# 1-Schematic_final_7_3d.net
KiCad netlist of a schematic drawn in EasyEDA
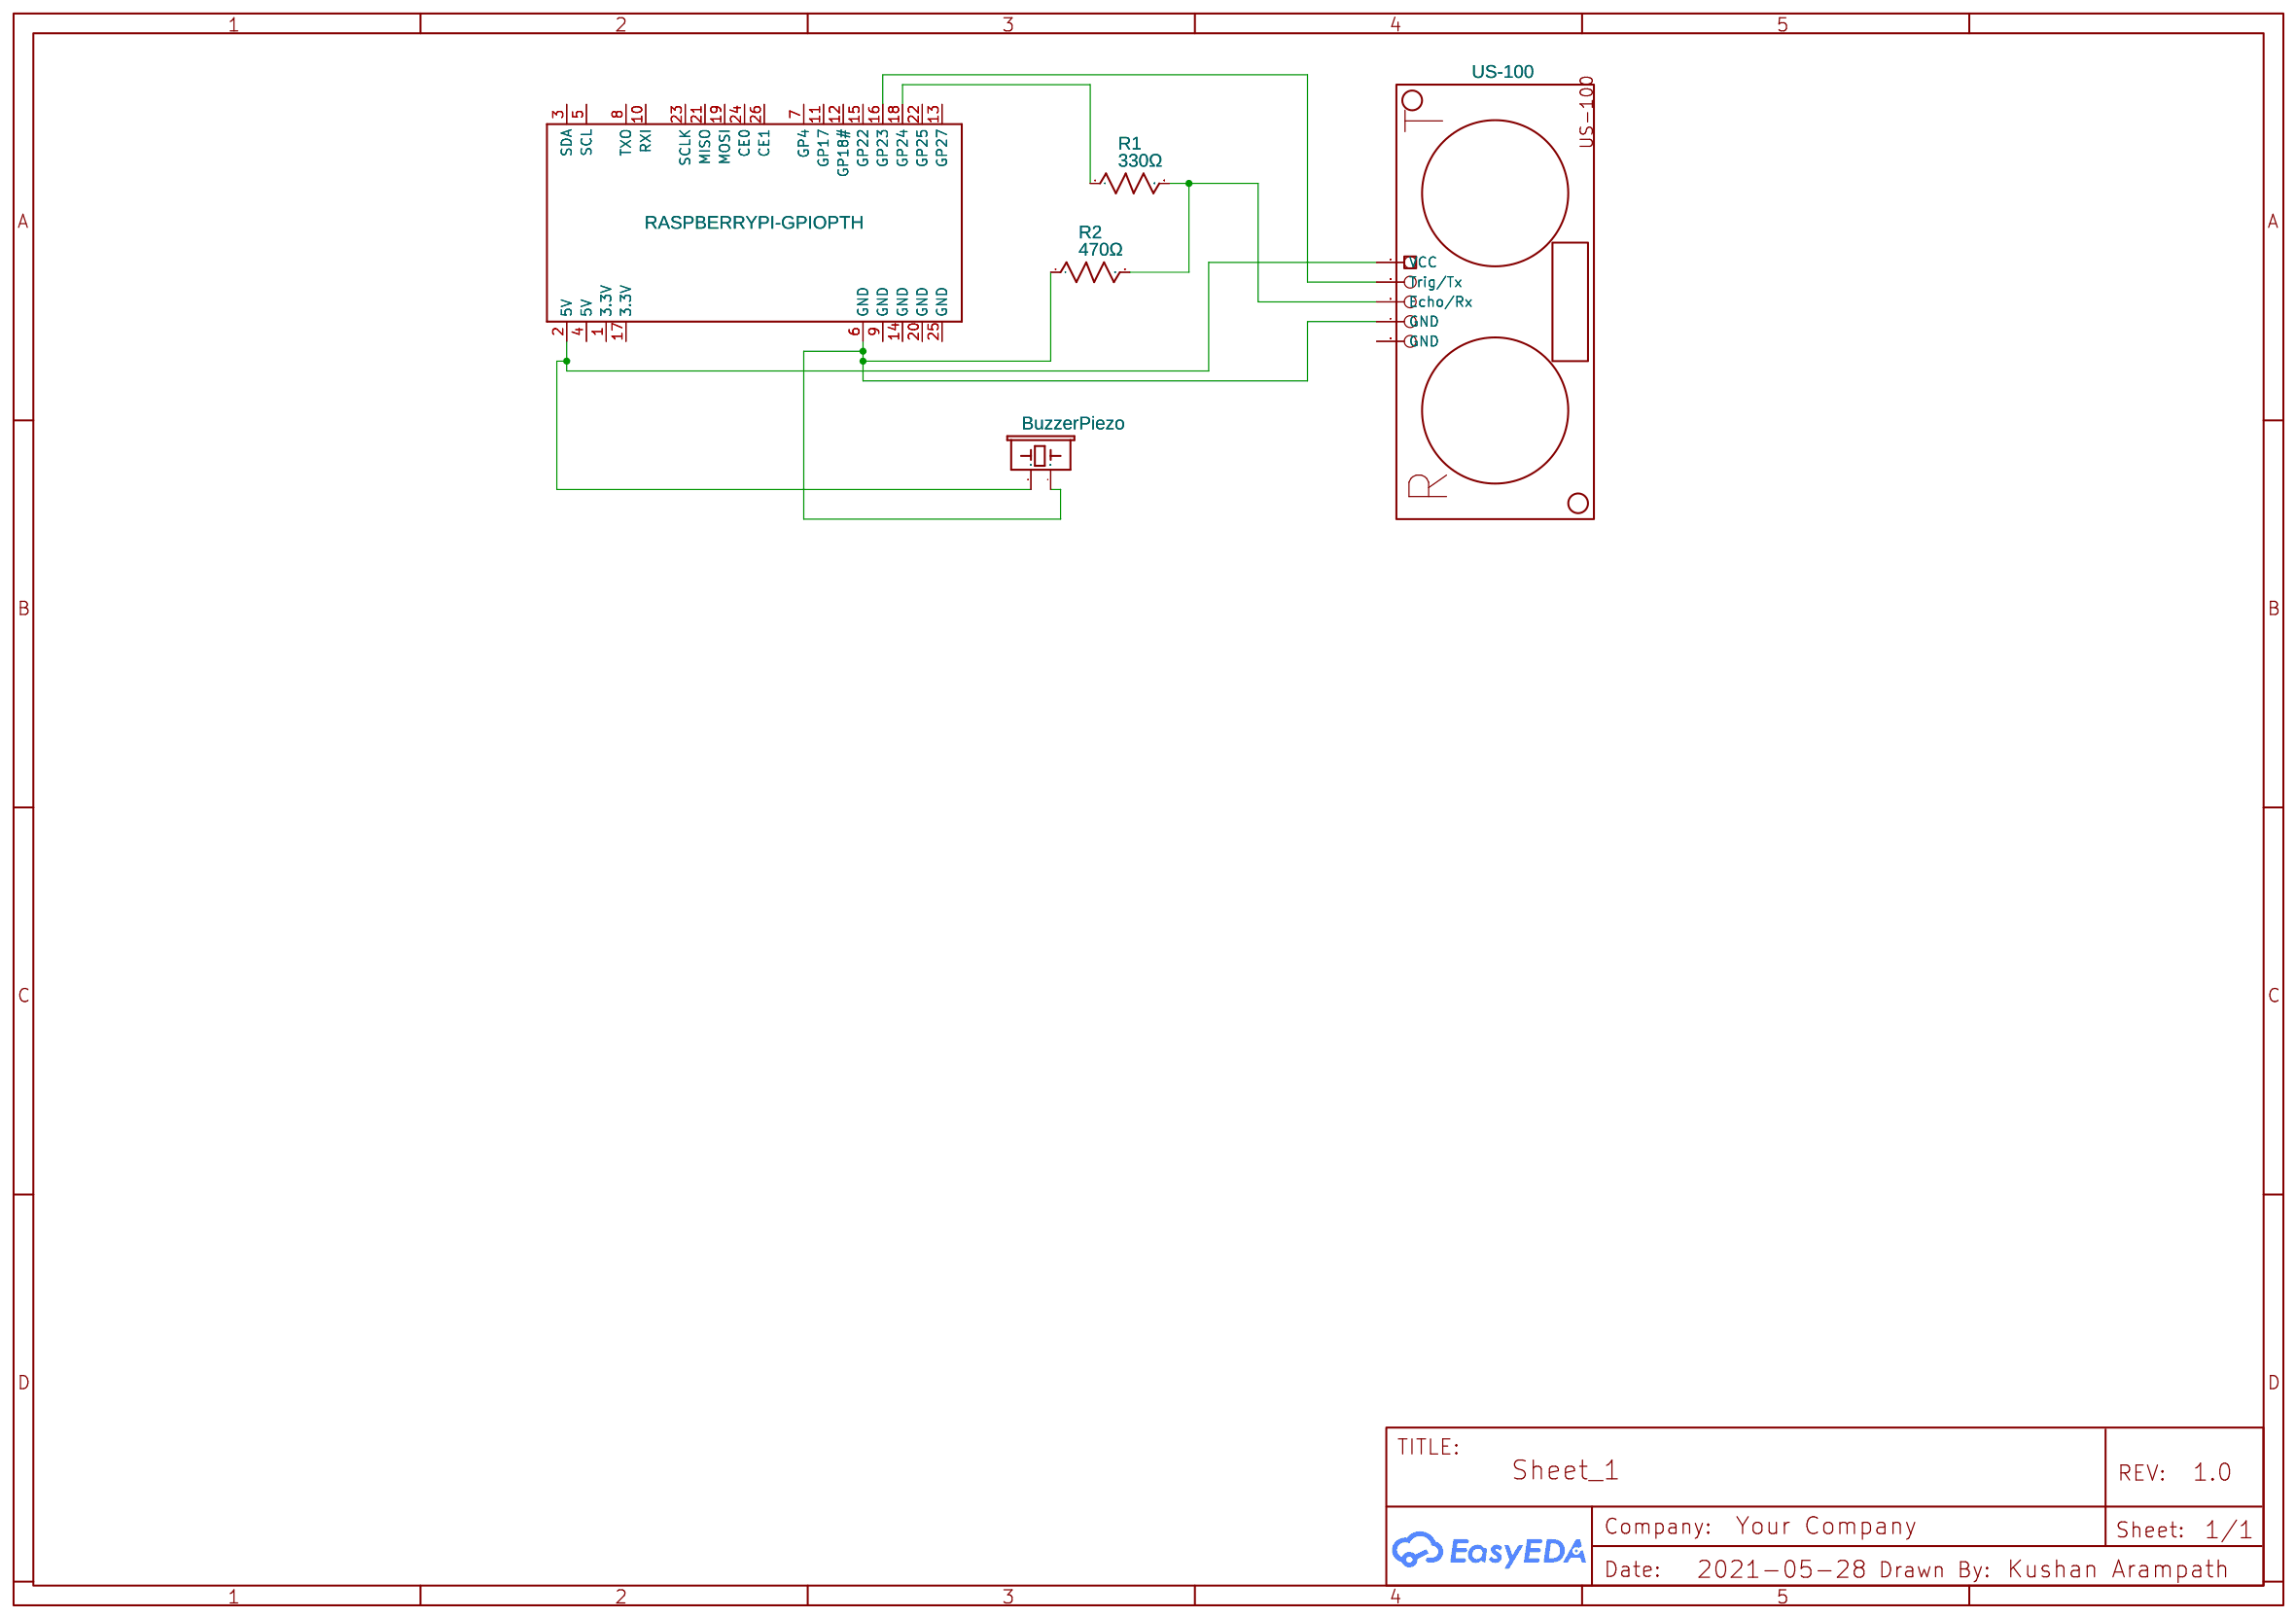
[diagram p0: schematic sheet]

(export (version "E")
  (design (tool "Eeschema 10.0.6"))
  (components
    (comp (ref "JP1") (value "RASPBERRYPI-GPIOPTH") (libsource (lib "") (part "RASPBERRYPI-GPIOPTH")))
    (comp (ref "R1") (value "330Ω") (libsource (lib "") (part "R_0603_US")))
    (comp (ref "R2") (value "470Ω") (libsource (lib "") (part "R_0603_US")))
    (comp (ref "SG1") (value "BuzzerPiezo") (libsource (lib "") (part "BUZZERSMD2-KIT")))
    (comp (ref "U1")
      (value "US-100")
      (fields (field (name "BOM_Manufacturer Part") "--"))
      (libsource (lib "") (part "US-100"))
    )
  )
  (nets
    (net (code "1") (name "Net-(JP1-GP23)") (class "Default")
      (node (ref "JP1") (pin "16") (pinfunction "GP23_16") (pintype "unspecified"))
      (node (ref "U1") (pin "2") (pinfunction "Trig/Tx_2") (pintype "output"))
    )
    (net (code "2") (name "Net-(JP1-GP24)") (class "Default")
      (node (ref "JP1") (pin "18") (pinfunction "GP24_18") (pintype "unspecified"))
      (node (ref "R1") (pin "1") (pinfunction "1_1") (pintype "unspecified"))
    )
    (net (code "3") (name "Net-(SG1-1)") (class "Default")
      (node (ref "JP1") (pin "2") (pinfunction "5V_2") (pintype "passive"))
      (node (ref "SG1") (pin "+") (pinfunction "1_+") (pintype "unspecified"))
      (node (ref "U1") (pin "1") (pinfunction "VCC_1") (pintype "passive"))
    )
    (net (code "4") (name "Net-(SG1-2)") (class "Default")
      (node (ref "JP1") (pin "6") (pinfunction "GND_6") (pintype "passive"))
      (node (ref "R2") (pin "1") (pinfunction "1_1") (pintype "unspecified"))
      (node (ref "SG1") (pin "-") (pinfunction "2_-") (pintype "unspecified"))
      (node (ref "U1") (pin "4") (pinfunction "GND_4") (pintype "unspecified"))
    )
    (net (code "5") (name "Net-(U1-Echo{slash}Rx)") (class "Default")
      (node (ref "R1") (pin "2") (pinfunction "2_2") (pintype "unspecified"))
      (node (ref "R2") (pin "2") (pinfunction "2_2") (pintype "unspecified"))
      (node (ref "U1") (pin "3") (pinfunction "Echo/Rx_3") (pintype "input"))
    )
    (net (code "6") (name "unconnected-(JP1-3.3V-Pad1)") (class "Default")
      (node (ref "JP1") (pin "1") (pinfunction "3.3V_1") (pintype "passive"))
    )
    (net (code "7") (name "unconnected-(JP1-3.3V-Pad17)") (class "Default")
      (node (ref "JP1") (pin "17") (pinfunction "3.3V_17") (pintype "passive"))
    )
    (net (code "8") (name "unconnected-(JP1-5V-Pad4)") (class "Default")
      (node (ref "JP1") (pin "4") (pinfunction "5V_4") (pintype "passive"))
    )
    (net (code "9") (name "unconnected-(JP1-CE0-Pad24)") (class "Default")
      (node (ref "JP1") (pin "24") (pinfunction "CE0_24") (pintype "output"))
    )
    (net (code "10") (name "unconnected-(JP1-CE1-Pad26)") (class "Default")
      (node (ref "JP1") (pin "26") (pinfunction "CE1_26") (pintype "output"))
    )
    (net (code "11") (name "unconnected-(JP1-GND-Pad9)") (class "Default")
      (node (ref "JP1") (pin "9") (pinfunction "GND_9") (pintype "passive"))
    )
    (net (code "12") (name "unconnected-(JP1-GND-Pad14)") (class "Default")
      (node (ref "JP1") (pin "14") (pinfunction "GND_14") (pintype "passive"))
    )
    (net (code "13") (name "unconnected-(JP1-GND-Pad20)") (class "Default")
      (node (ref "JP1") (pin "20") (pinfunction "GND_20") (pintype "passive"))
    )
    (net (code "14") (name "unconnected-(JP1-GND-Pad25)") (class "Default")
      (node (ref "JP1") (pin "25") (pinfunction "GND_25") (pintype "passive"))
    )
    (net (code "15") (name "unconnected-(JP1-GP4-Pad7)") (class "Default")
      (node (ref "JP1") (pin "7") (pinfunction "GP4_7") (pintype "unspecified"))
    )
    (net (code "16") (name "unconnected-(JP1-GP17-Pad11)") (class "Default")
      (node (ref "JP1") (pin "11") (pinfunction "GP17_11") (pintype "unspecified"))
    )
    (net (code "17") (name "unconnected-(JP1-GP18#-Pad12)") (class "Default")
      (node (ref "JP1") (pin "12") (pinfunction "GP18#_12") (pintype "unspecified"))
    )
    (net (code "18") (name "unconnected-(JP1-GP22-Pad15)") (class "Default")
      (node (ref "JP1") (pin "15") (pinfunction "GP22_15") (pintype "unspecified"))
    )
    (net (code "19") (name "unconnected-(JP1-GP25-Pad22)") (class "Default")
      (node (ref "JP1") (pin "22") (pinfunction "GP25_22") (pintype "unspecified"))
    )
    (net (code "20") (name "unconnected-(JP1-GP27-Pad13)") (class "Default")
      (node (ref "JP1") (pin "13") (pinfunction "GP27_13") (pintype "unspecified"))
    )
    (net (code "21") (name "unconnected-(JP1-MISO-Pad21)") (class "Default")
      (node (ref "JP1") (pin "21") (pinfunction "MISO_21") (pintype "input"))
    )
    (net (code "22") (name "unconnected-(JP1-MOSI-Pad19)") (class "Default")
      (node (ref "JP1") (pin "19") (pinfunction "MOSI_19") (pintype "output"))
    )
    (net (code "23") (name "unconnected-(JP1-RXI-Pad10)") (class "Default")
      (node (ref "JP1") (pin "10") (pinfunction "RXI_10") (pintype "input"))
    )
    (net (code "24") (name "unconnected-(JP1-SCL-Pad5)") (class "Default")
      (node (ref "JP1") (pin "5") (pinfunction "SCL_5") (pintype "unspecified"))
    )
    (net (code "25") (name "unconnected-(JP1-SCLK-Pad23)") (class "Default")
      (node (ref "JP1") (pin "23") (pinfunction "SCLK_23") (pintype "output"))
    )
    (net (code "26") (name "unconnected-(JP1-SDA-Pad3)") (class "Default")
      (node (ref "JP1") (pin "3") (pinfunction "SDA_3") (pintype "unspecified"))
    )
    (net (code "27") (name "unconnected-(JP1-TXO-Pad8)") (class "Default")
      (node (ref "JP1") (pin "8") (pinfunction "TXO_8") (pintype "output"))
    )
    (net (code "28") (name "unconnected-(U1-GND-Pad5)") (class "Default")
      (node (ref "U1") (pin "5") (pinfunction "GND_5") (pintype "unspecified"))
    )
  )
)
